# LED_BOARD_1st_Iteration.net
KiCad netlist of a schematic drawn in EAGLE
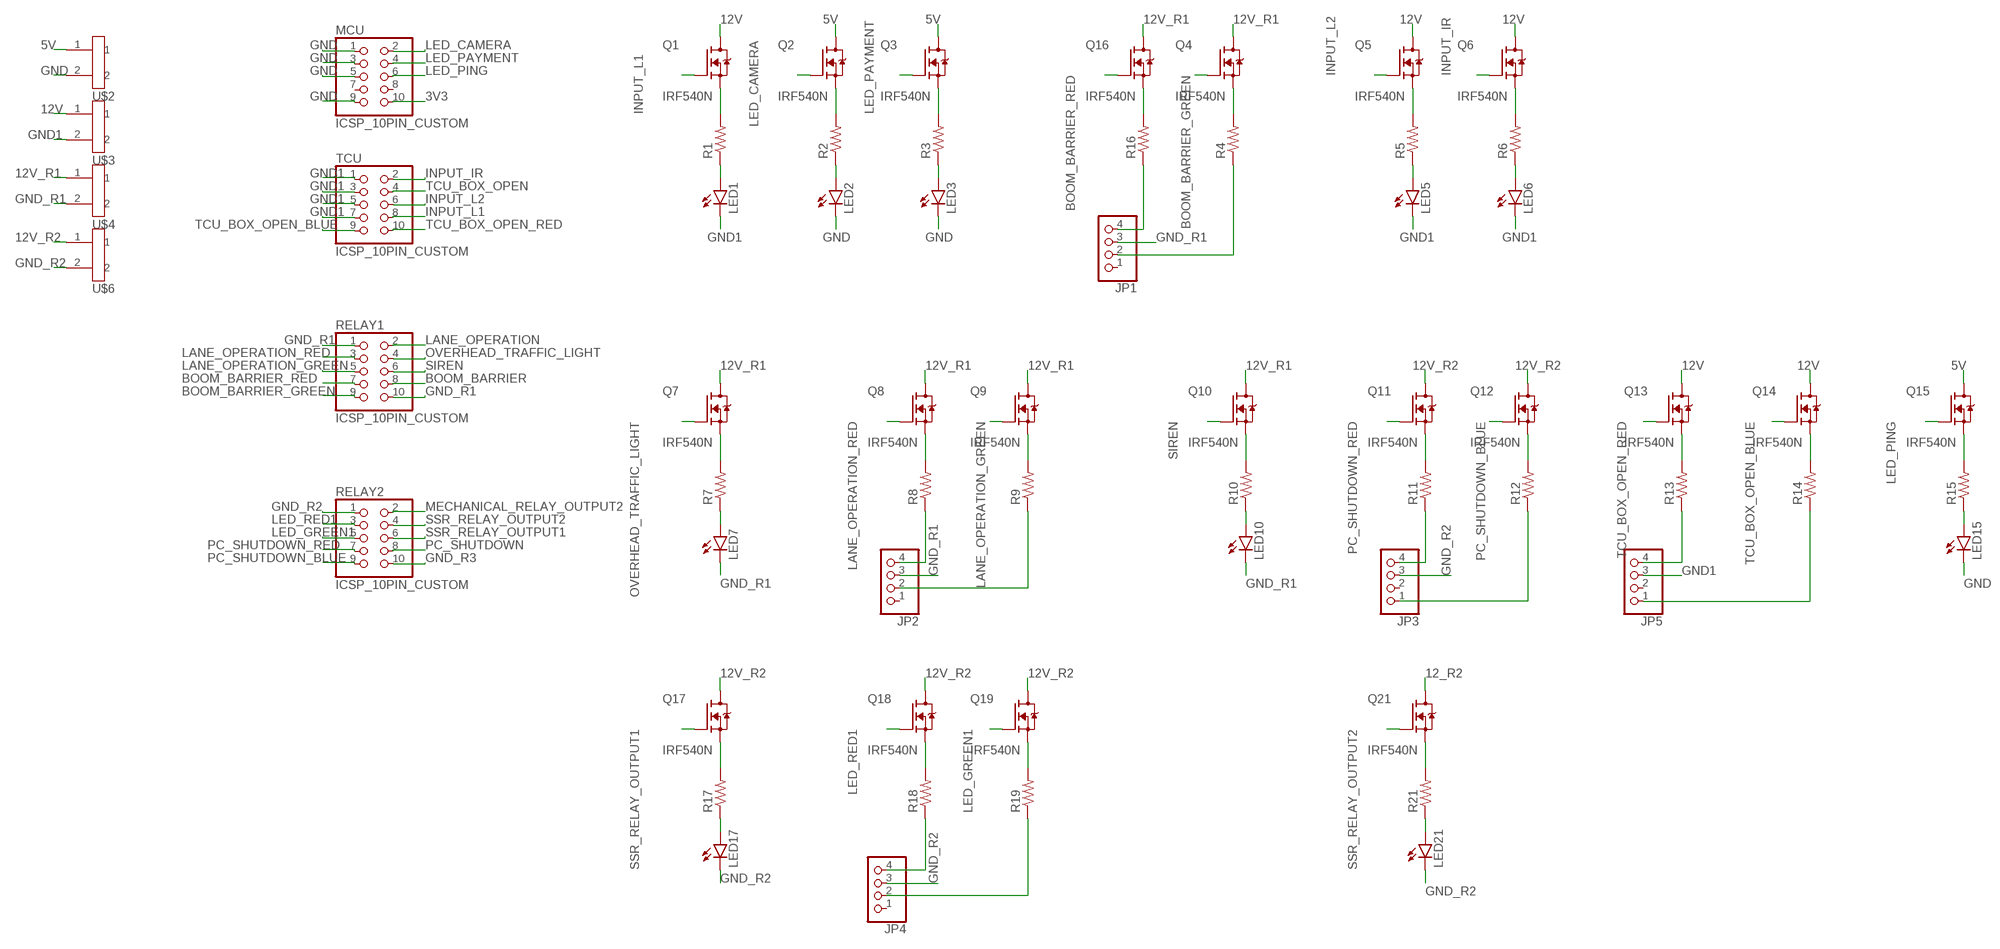
[diagram p0: schematic, sheet 1]

(export (version "E")
  (design (tool "Eeschema 10.0.6"))
  (components
    (comp (ref "JP1")
      (value "PINHD-1X4")
      (footprint "eagle-import:1X04")
      (libsource (lib "eagle-import") (part "PINHD-1X4"))
    )
    (comp (ref "JP2")
      (value "PINHD-1X4")
      (footprint "eagle-import:1X04")
      (libsource (lib "eagle-import") (part "PINHD-1X4"))
    )
    (comp (ref "JP3")
      (value "PINHD-1X4")
      (footprint "eagle-import:1X04")
      (libsource (lib "eagle-import") (part "PINHD-1X4"))
    )
    (comp (ref "JP4")
      (value "PINHD-1X4")
      (footprint "eagle-import:1X04")
      (libsource (lib "eagle-import") (part "PINHD-1X4"))
    )
    (comp (ref "JP5")
      (value "PINHD-1X4")
      (footprint "eagle-import:1X04")
      (libsource (lib "eagle-import") (part "PINHD-1X4"))
    )
    (comp (ref "LED1")
      (value "LED")
      (footprint "eagle-import:LED")
      (libsource (lib "eagle-import") (part "LED"))
    )
    (comp (ref "LED2")
      (value "LED")
      (footprint "eagle-import:LED")
      (libsource (lib "eagle-import") (part "LED"))
    )
    (comp (ref "LED3")
      (value "LED")
      (footprint "eagle-import:LED")
      (libsource (lib "eagle-import") (part "LED"))
    )
    (comp (ref "LED5")
      (value "LED")
      (footprint "eagle-import:LED")
      (libsource (lib "eagle-import") (part "LED"))
    )
    (comp (ref "LED6")
      (value "LED")
      (footprint "eagle-import:LED")
      (libsource (lib "eagle-import") (part "LED"))
    )
    (comp (ref "LED7")
      (value "LED")
      (footprint "eagle-import:LED")
      (libsource (lib "eagle-import") (part "LED"))
    )
    (comp (ref "LED10")
      (value "LED")
      (footprint "eagle-import:LED")
      (libsource (lib "eagle-import") (part "LED"))
    )
    (comp (ref "LED15")
      (value "LED")
      (footprint "eagle-import:LED")
      (libsource (lib "eagle-import") (part "LED"))
    )
    (comp (ref "LED17")
      (value "LED")
      (footprint "eagle-import:LED")
      (libsource (lib "eagle-import") (part "LED"))
    )
    (comp (ref "LED21")
      (value "LED")
      (footprint "eagle-import:LED")
      (libsource (lib "eagle-import") (part "LED"))
    )
    (comp (ref "MCU")
      (value "ICSP_10PIN_CUSTOM")
      (footprint "eagle-import:ICSP_10PIN_CUSTOM")
      (libsource (lib "eagle-import") (part "ICSP_10PIN_CUSTOM"))
    )
    (comp (ref "Q1")
      (value "IRF540N")
      (footprint "eagle-import:TO254P1054X469X1930-3")
      (fields (field (name "MF") "Infineon Technologies"))
      (libsource (lib "eagle-import") (part "IRF540N"))
    )
    (comp (ref "Q2")
      (value "IRF540N")
      (footprint "eagle-import:TO254P1054X469X1930-3")
      (fields (field (name "MF") "Infineon Technologies"))
      (libsource (lib "eagle-import") (part "IRF540N"))
    )
    (comp (ref "Q3")
      (value "IRF540N")
      (footprint "eagle-import:TO254P1054X469X1930-3")
      (fields (field (name "MF") "Infineon Technologies"))
      (libsource (lib "eagle-import") (part "IRF540N"))
    )
    (comp (ref "Q4")
      (value "IRF540N")
      (footprint "eagle-import:TO254P1054X469X1930-3")
      (fields (field (name "MF") "Infineon Technologies"))
      (libsource (lib "eagle-import") (part "IRF540N"))
    )
    (comp (ref "Q5")
      (value "IRF540N")
      (footprint "eagle-import:TO254P1054X469X1930-3")
      (fields (field (name "MF") "Infineon Technologies"))
      (libsource (lib "eagle-import") (part "IRF540N"))
    )
    (comp (ref "Q6")
      (value "IRF540N")
      (footprint "eagle-import:TO254P1054X469X1930-3")
      (fields (field (name "MF") "Infineon Technologies"))
      (libsource (lib "eagle-import") (part "IRF540N"))
    )
    (comp (ref "Q7")
      (value "IRF540N")
      (footprint "eagle-import:TO254P1054X469X1930-3")
      (fields (field (name "MF") "Infineon Technologies"))
      (libsource (lib "eagle-import") (part "IRF540N"))
    )
    (comp (ref "Q8")
      (value "IRF540N")
      (footprint "eagle-import:TO254P1054X469X1930-3")
      (fields (field (name "MF") "Infineon Technologies"))
      (libsource (lib "eagle-import") (part "IRF540N"))
    )
    (comp (ref "Q9")
      (value "IRF540N")
      (footprint "eagle-import:TO254P1054X469X1930-3")
      (fields (field (name "MF") "Infineon Technologies"))
      (libsource (lib "eagle-import") (part "IRF540N"))
    )
    (comp (ref "Q10")
      (value "IRF540N")
      (footprint "eagle-import:TO254P1054X469X1930-3")
      (fields (field (name "MF") "Infineon Technologies"))
      (libsource (lib "eagle-import") (part "IRF540N"))
    )
    (comp (ref "Q11")
      (value "IRF540N")
      (footprint "eagle-import:TO254P1054X469X1930-3")
      (fields (field (name "MF") "Infineon Technologies"))
      (libsource (lib "eagle-import") (part "IRF540N"))
    )
    (comp (ref "Q12")
      (value "IRF540N")
      (footprint "eagle-import:TO254P1054X469X1930-3")
      (fields (field (name "MF") "Infineon Technologies"))
      (libsource (lib "eagle-import") (part "IRF540N"))
    )
    (comp (ref "Q13")
      (value "IRF540N")
      (footprint "eagle-import:TO254P1054X469X1930-3")
      (fields (field (name "MF") "Infineon Technologies"))
      (libsource (lib "eagle-import") (part "IRF540N"))
    )
    (comp (ref "Q14")
      (value "IRF540N")
      (footprint "eagle-import:TO254P1054X469X1930-3")
      (fields (field (name "MF") "Infineon Technologies"))
      (libsource (lib "eagle-import") (part "IRF540N"))
    )
    (comp (ref "Q15")
      (value "IRF540N")
      (footprint "eagle-import:TO254P1054X469X1930-3")
      (fields (field (name "MF") "Infineon Technologies"))
      (libsource (lib "eagle-import") (part "IRF540N"))
    )
    (comp (ref "Q16")
      (value "IRF540N")
      (footprint "eagle-import:TO254P1054X469X1930-3")
      (fields (field (name "MF") "Infineon Technologies"))
      (libsource (lib "eagle-import") (part "IRF540N"))
    )
    (comp (ref "Q17")
      (value "IRF540N")
      (footprint "eagle-import:TO254P1054X469X1930-3")
      (fields (field (name "MF") "Infineon Technologies"))
      (libsource (lib "eagle-import") (part "IRF540N"))
    )
    (comp (ref "Q18")
      (value "IRF540N")
      (footprint "eagle-import:TO254P1054X469X1930-3")
      (fields (field (name "MF") "Infineon Technologies"))
      (libsource (lib "eagle-import") (part "IRF540N"))
    )
    (comp (ref "Q19")
      (value "IRF540N")
      (footprint "eagle-import:TO254P1054X469X1930-3")
      (fields (field (name "MF") "Infineon Technologies"))
      (libsource (lib "eagle-import") (part "IRF540N"))
    )
    (comp (ref "Q21")
      (value "IRF540N")
      (footprint "eagle-import:TO254P1054X469X1930-3")
      (fields (field (name "MF") "Infineon Technologies"))
      (libsource (lib "eagle-import") (part "IRF540N"))
    )
    (comp (ref "R1")
      (value "RESISTOR")
      (footprint "eagle-import:RESISTOR")
      (libsource (lib "eagle-import") (part "RESISTOR"))
    )
    (comp (ref "R2")
      (value "RESISTOR")
      (footprint "eagle-import:RESISTOR")
      (libsource (lib "eagle-import") (part "RESISTOR"))
    )
    (comp (ref "R3")
      (value "RESISTOR")
      (footprint "eagle-import:RESISTOR")
      (libsource (lib "eagle-import") (part "RESISTOR"))
    )
    (comp (ref "R4")
      (value "RESISTOR")
      (footprint "eagle-import:RESISTOR")
      (libsource (lib "eagle-import") (part "RESISTOR"))
    )
    (comp (ref "R5")
      (value "RESISTOR")
      (footprint "eagle-import:RESISTOR")
      (libsource (lib "eagle-import") (part "RESISTOR"))
    )
    (comp (ref "R6")
      (value "RESISTOR")
      (footprint "eagle-import:RESISTOR")
      (libsource (lib "eagle-import") (part "RESISTOR"))
    )
    (comp (ref "R7")
      (value "RESISTOR")
      (footprint "eagle-import:RESISTOR")
      (libsource (lib "eagle-import") (part "RESISTOR"))
    )
    (comp (ref "R8")
      (value "RESISTOR")
      (footprint "eagle-import:RESISTOR")
      (libsource (lib "eagle-import") (part "RESISTOR"))
    )
    (comp (ref "R9")
      (value "RESISTOR")
      (footprint "eagle-import:RESISTOR")
      (libsource (lib "eagle-import") (part "RESISTOR"))
    )
    (comp (ref "R10")
      (value "RESISTOR")
      (footprint "eagle-import:RESISTOR")
      (libsource (lib "eagle-import") (part "RESISTOR"))
    )
    (comp (ref "R11")
      (value "RESISTOR")
      (footprint "eagle-import:RESISTOR")
      (libsource (lib "eagle-import") (part "RESISTOR"))
    )
    (comp (ref "R12")
      (value "RESISTOR")
      (footprint "eagle-import:RESISTOR")
      (libsource (lib "eagle-import") (part "RESISTOR"))
    )
    (comp (ref "R13")
      (value "RESISTOR")
      (footprint "eagle-import:RESISTOR")
      (libsource (lib "eagle-import") (part "RESISTOR"))
    )
    (comp (ref "R14")
      (value "RESISTOR")
      (footprint "eagle-import:RESISTOR")
      (libsource (lib "eagle-import") (part "RESISTOR"))
    )
    (comp (ref "R15")
      (value "RESISTOR")
      (footprint "eagle-import:RESISTOR")
      (libsource (lib "eagle-import") (part "RESISTOR"))
    )
    (comp (ref "R16")
      (value "RESISTOR")
      (footprint "eagle-import:RESISTOR")
      (libsource (lib "eagle-import") (part "RESISTOR"))
    )
    (comp (ref "R17")
      (value "RESISTOR")
      (footprint "eagle-import:RESISTOR")
      (libsource (lib "eagle-import") (part "RESISTOR"))
    )
    (comp (ref "R18")
      (value "RESISTOR")
      (footprint "eagle-import:RESISTOR")
      (libsource (lib "eagle-import") (part "RESISTOR"))
    )
    (comp (ref "R19")
      (value "RESISTOR")
      (footprint "eagle-import:RESISTOR")
      (libsource (lib "eagle-import") (part "RESISTOR"))
    )
    (comp (ref "R21")
      (value "RESISTOR")
      (footprint "eagle-import:RESISTOR")
      (libsource (lib "eagle-import") (part "RESISTOR"))
    )
    (comp (ref "RELAY1")
      (value "ICSP_10PIN_CUSTOM")
      (footprint "eagle-import:ICSP_10PIN_CUSTOM")
      (libsource (lib "eagle-import") (part "ICSP_10PIN_CUSTOM"))
    )
    (comp (ref "RELAY2")
      (value "ICSP_10PIN_CUSTOM")
      (footprint "eagle-import:ICSP_10PIN_CUSTOM")
      (libsource (lib "eagle-import") (part "ICSP_10PIN_CUSTOM"))
    )
    (comp (ref "TCU")
      (value "ICSP_10PIN_CUSTOM")
      (footprint "eagle-import:ICSP_10PIN_CUSTOM")
      (libsource (lib "eagle-import") (part "ICSP_10PIN_CUSTOM"))
    )
    (comp (ref "U$2")
      (value "GREEN_PLUG_90_2")
      (footprint "eagle-import:GREEN_PLUG_90_2")
      (libsource (lib "eagle-import") (part "GREEN_PLUG_90_2"))
    )
    (comp (ref "U$3")
      (value "GREEN_PLUG_90_2")
      (footprint "eagle-import:GREEN_PLUG_90_2")
      (libsource (lib "eagle-import") (part "GREEN_PLUG_90_2"))
    )
    (comp (ref "U$4")
      (value "GREEN_PLUG_90_2")
      (footprint "eagle-import:GREEN_PLUG_90_2")
      (libsource (lib "eagle-import") (part "GREEN_PLUG_90_2"))
    )
    (comp (ref "U$6")
      (value "GREEN_PLUG_90_2")
      (footprint "eagle-import:GREEN_PLUG_90_2")
      (libsource (lib "eagle-import") (part "GREEN_PLUG_90_2"))
    )
  )
  (nets
    (net (code "1") (name "/3V3") (class "Default")
      (node (ref "MCU") (pin "10") (pinfunction "10_10") (pintype "passive"))
    )
    (net (code "2") (name "/5V") (class "Default")
      (node (ref "Q15") (pin "2") (pinfunction "D_2") (pintype "passive"))
      (node (ref "Q2") (pin "2") (pinfunction "D_2") (pintype "passive"))
      (node (ref "Q3") (pin "2") (pinfunction "D_2") (pintype "passive"))
      (node (ref "U$2") (pin "1") (pinfunction "1_1") (pintype "passive"))
    )
    (net (code "3") (name "/12V") (class "Default")
      (node (ref "Q1") (pin "2") (pinfunction "D_2") (pintype "passive"))
      (node (ref "Q13") (pin "2") (pinfunction "D_2") (pintype "passive"))
      (node (ref "Q14") (pin "2") (pinfunction "D_2") (pintype "passive"))
      (node (ref "Q5") (pin "2") (pinfunction "D_2") (pintype "passive"))
      (node (ref "Q6") (pin "2") (pinfunction "D_2") (pintype "passive"))
      (node (ref "U$3") (pin "1") (pinfunction "1_1") (pintype "passive"))
    )
    (net (code "4") (name "/12V_R1") (class "Default")
      (node (ref "Q10") (pin "2") (pinfunction "D_2") (pintype "passive"))
      (node (ref "Q16") (pin "2") (pinfunction "D_2") (pintype "passive"))
      (node (ref "Q4") (pin "2") (pinfunction "D_2") (pintype "passive"))
      (node (ref "Q7") (pin "2") (pinfunction "D_2") (pintype "passive"))
      (node (ref "Q8") (pin "2") (pinfunction "D_2") (pintype "passive"))
      (node (ref "Q9") (pin "2") (pinfunction "D_2") (pintype "passive"))
      (node (ref "U$4") (pin "1") (pinfunction "1_1") (pintype "passive"))
    )
    (net (code "5") (name "/12V_R2") (class "Default")
      (node (ref "Q11") (pin "2") (pinfunction "D_2") (pintype "passive"))
      (node (ref "Q12") (pin "2") (pinfunction "D_2") (pintype "passive"))
      (node (ref "Q17") (pin "2") (pinfunction "D_2") (pintype "passive"))
      (node (ref "Q18") (pin "2") (pinfunction "D_2") (pintype "passive"))
      (node (ref "Q19") (pin "2") (pinfunction "D_2") (pintype "passive"))
      (node (ref "U$6") (pin "1") (pinfunction "1_1") (pintype "passive"))
    )
    (net (code "6") (name "/12_R2") (class "Default")
      (node (ref "Q21") (pin "2") (pinfunction "D_2") (pintype "passive"))
    )
    (net (code "7") (name "/BOOM_BARRIER") (class "Default")
      (node (ref "RELAY1") (pin "8") (pinfunction "8_8") (pintype "passive"))
    )
    (net (code "8") (name "/BOOM_BARRIER_GREEN") (class "Default")
      (node (ref "Q4") (pin "1") (pinfunction "G_1") (pintype "passive"))
      (node (ref "RELAY1") (pin "9") (pinfunction "9_9") (pintype "passive"))
    )
    (net (code "9") (name "/BOOM_BARRIER_RED") (class "Default")
      (node (ref "Q16") (pin "1") (pinfunction "G_1") (pintype "passive"))
      (node (ref "RELAY1") (pin "7") (pinfunction "7_7") (pintype "passive"))
    )
    (net (code "10") (name "/GND") (class "Default")
      (node (ref "LED15") (pin "K") (pinfunction "C_K") (pintype "passive"))
      (node (ref "LED2") (pin "K") (pinfunction "C_K") (pintype "passive"))
      (node (ref "LED3") (pin "K") (pinfunction "C_K") (pintype "passive"))
      (node (ref "MCU") (pin "1") (pinfunction "1_1") (pintype "passive"))
      (node (ref "MCU") (pin "3") (pinfunction "3_3") (pintype "passive"))
      (node (ref "MCU") (pin "5") (pinfunction "5_5") (pintype "passive"))
      (node (ref "MCU") (pin "9") (pinfunction "9_9") (pintype "passive"))
      (node (ref "U$2") (pin "2") (pinfunction "2_2") (pintype "passive"))
    )
    (net (code "11") (name "/GND1") (class "Default")
      (node (ref "JP5") (pin "3") (pinfunction "3_3") (pintype "passive"))
      (node (ref "LED1") (pin "K") (pinfunction "C_K") (pintype "passive"))
      (node (ref "LED5") (pin "K") (pinfunction "C_K") (pintype "passive"))
      (node (ref "LED6") (pin "K") (pinfunction "C_K") (pintype "passive"))
      (node (ref "TCU") (pin "1") (pinfunction "1_1") (pintype "passive"))
      (node (ref "TCU") (pin "3") (pinfunction "3_3") (pintype "passive"))
      (node (ref "TCU") (pin "5") (pinfunction "5_5") (pintype "passive"))
      (node (ref "TCU") (pin "7") (pinfunction "7_7") (pintype "passive"))
      (node (ref "U$3") (pin "2") (pinfunction "2_2") (pintype "passive"))
    )
    (net (code "12") (name "/GND_R1") (class "Default")
      (node (ref "JP1") (pin "3") (pinfunction "3_3") (pintype "passive"))
      (node (ref "JP2") (pin "3") (pinfunction "3_3") (pintype "passive"))
      (node (ref "LED10") (pin "K") (pinfunction "C_K") (pintype "passive"))
      (node (ref "LED7") (pin "K") (pinfunction "C_K") (pintype "passive"))
      (node (ref "RELAY1") (pin "1") (pinfunction "1_1") (pintype "passive"))
      (node (ref "RELAY1") (pin "10") (pinfunction "10_10") (pintype "passive"))
      (node (ref "U$4") (pin "2") (pinfunction "2_2") (pintype "passive"))
    )
    (net (code "13") (name "/GND_R2") (class "Default")
      (node (ref "JP3") (pin "3") (pinfunction "3_3") (pintype "passive"))
      (node (ref "JP4") (pin "3") (pinfunction "3_3") (pintype "passive"))
      (node (ref "LED17") (pin "K") (pinfunction "C_K") (pintype "passive"))
      (node (ref "LED21") (pin "K") (pinfunction "C_K") (pintype "passive"))
      (node (ref "RELAY2") (pin "1") (pinfunction "1_1") (pintype "passive"))
      (node (ref "U$6") (pin "2") (pinfunction "2_2") (pintype "passive"))
    )
    (net (code "14") (name "/GND_R3") (class "Default")
      (node (ref "RELAY2") (pin "10") (pinfunction "10_10") (pintype "passive"))
    )
    (net (code "15") (name "/INPUT_IR") (class "Default")
      (node (ref "Q6") (pin "1") (pinfunction "G_1") (pintype "passive"))
      (node (ref "TCU") (pin "2") (pinfunction "2_2") (pintype "passive"))
    )
    (net (code "16") (name "/INPUT_L1") (class "Default")
      (node (ref "Q1") (pin "1") (pinfunction "G_1") (pintype "passive"))
      (node (ref "TCU") (pin "8") (pinfunction "8_8") (pintype "passive"))
    )
    (net (code "17") (name "/INPUT_L2") (class "Default")
      (node (ref "Q5") (pin "1") (pinfunction "G_1") (pintype "passive"))
      (node (ref "TCU") (pin "6") (pinfunction "6_6") (pintype "passive"))
    )
    (net (code "18") (name "/LANE_OPERATION") (class "Default")
      (node (ref "RELAY1") (pin "2") (pinfunction "2_2") (pintype "passive"))
    )
    (net (code "19") (name "/LANE_OPERATION_GREEN") (class "Default")
      (node (ref "Q9") (pin "1") (pinfunction "G_1") (pintype "passive"))
      (node (ref "RELAY1") (pin "5") (pinfunction "5_5") (pintype "passive"))
    )
    (net (code "20") (name "/LANE_OPERATION_RED") (class "Default")
      (node (ref "Q8") (pin "1") (pinfunction "G_1") (pintype "passive"))
      (node (ref "RELAY1") (pin "3") (pinfunction "3_3") (pintype "passive"))
    )
    (net (code "21") (name "/LED_CAMERA") (class "Default")
      (node (ref "MCU") (pin "2") (pinfunction "2_2") (pintype "passive"))
      (node (ref "Q2") (pin "1") (pinfunction "G_1") (pintype "passive"))
    )
    (net (code "22") (name "/LED_GREEN1") (class "Default")
      (node (ref "Q19") (pin "1") (pinfunction "G_1") (pintype "passive"))
      (node (ref "RELAY2") (pin "5") (pinfunction "5_5") (pintype "passive"))
    )
    (net (code "23") (name "/LED_PAYMENT") (class "Default")
      (node (ref "MCU") (pin "4") (pinfunction "4_4") (pintype "passive"))
      (node (ref "Q3") (pin "1") (pinfunction "G_1") (pintype "passive"))
    )
    (net (code "24") (name "/LED_PING") (class "Default")
      (node (ref "MCU") (pin "6") (pinfunction "6_6") (pintype "passive"))
      (node (ref "Q15") (pin "1") (pinfunction "G_1") (pintype "passive"))
    )
    (net (code "25") (name "/LED_RED1") (class "Default")
      (node (ref "Q18") (pin "1") (pinfunction "G_1") (pintype "passive"))
      (node (ref "RELAY2") (pin "3") (pinfunction "3_3") (pintype "passive"))
    )
    (net (code "26") (name "/MECHANICAL_RELAY_OUTPUT2") (class "Default")
      (node (ref "RELAY2") (pin "2") (pinfunction "2_2") (pintype "passive"))
    )
    (net (code "27") (name "/OVERHEAD_TRAFFIC_LIGHT") (class "Default")
      (node (ref "Q7") (pin "1") (pinfunction "G_1") (pintype "passive"))
      (node (ref "RELAY1") (pin "4") (pinfunction "4_4") (pintype "passive"))
    )
    (net (code "28") (name "/PC_SHUTDOWN") (class "Default")
      (node (ref "RELAY2") (pin "8") (pinfunction "8_8") (pintype "passive"))
    )
    (net (code "29") (name "/PC_SHUTDOWN_BLUE") (class "Default")
      (node (ref "Q12") (pin "1") (pinfunction "G_1") (pintype "passive"))
      (node (ref "RELAY2") (pin "9") (pinfunction "9_9") (pintype "passive"))
    )
    (net (code "30") (name "/PC_SHUTDOWN_RED") (class "Default")
      (node (ref "Q11") (pin "1") (pinfunction "G_1") (pintype "passive"))
      (node (ref "RELAY2") (pin "7") (pinfunction "7_7") (pintype "passive"))
    )
    (net (code "31") (name "/SIREN") (class "Default")
      (node (ref "Q10") (pin "1") (pinfunction "G_1") (pintype "passive"))
      (node (ref "RELAY1") (pin "6") (pinfunction "6_6") (pintype "passive"))
    )
    (net (code "32") (name "/SSR_RELAY_OUTPUT1") (class "Default")
      (node (ref "Q17") (pin "1") (pinfunction "G_1") (pintype "passive"))
      (node (ref "RELAY2") (pin "6") (pinfunction "6_6") (pintype "passive"))
    )
    (net (code "33") (name "/SSR_RELAY_OUTPUT2") (class "Default")
      (node (ref "Q21") (pin "1") (pinfunction "G_1") (pintype "passive"))
      (node (ref "RELAY2") (pin "4") (pinfunction "4_4") (pintype "passive"))
    )
    (net (code "34") (name "/TCU_BOX_OPEN") (class "Default")
      (node (ref "TCU") (pin "4") (pinfunction "4_4") (pintype "passive"))
    )
    (net (code "35") (name "/TCU_BOX_OPEN_BLUE") (class "Default")
      (node (ref "Q14") (pin "1") (pinfunction "G_1") (pintype "passive"))
      (node (ref "TCU") (pin "9") (pinfunction "9_9") (pintype "passive"))
    )
    (net (code "36") (name "/TCU_BOX_OPEN_RED") (class "Default")
      (node (ref "Q13") (pin "1") (pinfunction "G_1") (pintype "passive"))
      (node (ref "TCU") (pin "10") (pinfunction "10_10") (pintype "passive"))
    )
    (net (code "37") (name "Net-(JP1-Pad2)") (class "Default")
      (node (ref "JP1") (pin "2") (pinfunction "2_2") (pintype "passive"))
      (node (ref "R4") (pin "1") (pinfunction "1_1") (pintype "passive"))
    )
    (net (code "38") (name "Net-(JP1-Pad4)") (class "Default")
      (node (ref "JP1") (pin "4") (pinfunction "4_4") (pintype "passive"))
      (node (ref "R16") (pin "1") (pinfunction "1_1") (pintype "passive"))
    )
    (net (code "39") (name "Net-(JP2-Pad2)") (class "Default")
      (node (ref "JP2") (pin "2") (pinfunction "2_2") (pintype "passive"))
      (node (ref "R9") (pin "1") (pinfunction "1_1") (pintype "passive"))
    )
    (net (code "40") (name "Net-(JP2-Pad4)") (class "Default")
      (node (ref "JP2") (pin "4") (pinfunction "4_4") (pintype "passive"))
      (node (ref "R8") (pin "1") (pinfunction "1_1") (pintype "passive"))
    )
    (net (code "41") (name "Net-(JP3-Pad1)") (class "Default")
      (node (ref "JP3") (pin "1") (pinfunction "1_1") (pintype "passive"))
      (node (ref "R12") (pin "1") (pinfunction "1_1") (pintype "passive"))
    )
    (net (code "42") (name "Net-(JP3-Pad4)") (class "Default")
      (node (ref "JP3") (pin "4") (pinfunction "4_4") (pintype "passive"))
      (node (ref "R11") (pin "1") (pinfunction "1_1") (pintype "passive"))
    )
    (net (code "43") (name "Net-(JP4-Pad2)") (class "Default")
      (node (ref "JP4") (pin "2") (pinfunction "2_2") (pintype "passive"))
      (node (ref "R19") (pin "1") (pinfunction "1_1") (pintype "passive"))
    )
    (net (code "44") (name "Net-(JP4-Pad4)") (class "Default")
      (node (ref "JP4") (pin "4") (pinfunction "4_4") (pintype "passive"))
      (node (ref "R18") (pin "1") (pinfunction "1_1") (pintype "passive"))
    )
    (net (code "45") (name "Net-(JP5-Pad1)") (class "Default")
      (node (ref "JP5") (pin "1") (pinfunction "1_1") (pintype "passive"))
      (node (ref "R14") (pin "1") (pinfunction "1_1") (pintype "passive"))
    )
    (net (code "46") (name "Net-(JP5-Pad4)") (class "Default")
      (node (ref "JP5") (pin "4") (pinfunction "4_4") (pintype "passive"))
      (node (ref "R13") (pin "1") (pinfunction "1_1") (pintype "passive"))
    )
    (net (code "47") (name "Net-(LED1-PadA)") (class "Default")
      (node (ref "LED1") (pin "A") (pinfunction "A_A") (pintype "passive"))
      (node (ref "R1") (pin "1") (pinfunction "1_1") (pintype "passive"))
    )
    (net (code "48") (name "Net-(LED2-PadA)") (class "Default")
      (node (ref "LED2") (pin "A") (pinfunction "A_A") (pintype "passive"))
      (node (ref "R2") (pin "1") (pinfunction "1_1") (pintype "passive"))
    )
    (net (code "49") (name "Net-(LED3-PadA)") (class "Default")
      (node (ref "LED3") (pin "A") (pinfunction "A_A") (pintype "passive"))
      (node (ref "R3") (pin "1") (pinfunction "1_1") (pintype "passive"))
    )
    (net (code "50") (name "Net-(LED5-PadA)") (class "Default")
      (node (ref "LED5") (pin "A") (pinfunction "A_A") (pintype "passive"))
      (node (ref "R5") (pin "1") (pinfunction "1_1") (pintype "passive"))
    )
    (net (code "51") (name "Net-(LED6-PadA)") (class "Default")
      (node (ref "LED6") (pin "A") (pinfunction "A_A") (pintype "passive"))
      (node (ref "R6") (pin "1") (pinfunction "1_1") (pintype "passive"))
    )
    (net (code "52") (name "Net-(LED7-PadA)") (class "Default")
      (node (ref "LED7") (pin "A") (pinfunction "A_A") (pintype "passive"))
      (node (ref "R7") (pin "1") (pinfunction "1_1") (pintype "passive"))
    )
    (net (code "53") (name "Net-(LED10-PadA)") (class "Default")
      (node (ref "LED10") (pin "A") (pinfunction "A_A") (pintype "passive"))
      (node (ref "R10") (pin "1") (pinfunction "1_1") (pintype "passive"))
    )
    (net (code "54") (name "Net-(LED15-PadA)") (class "Default")
      (node (ref "LED15") (pin "A") (pinfunction "A_A") (pintype "passive"))
      (node (ref "R15") (pin "1") (pinfunction "1_1") (pintype "passive"))
    )
    (net (code "55") (name "Net-(LED17-PadA)") (class "Default")
      (node (ref "LED17") (pin "A") (pinfunction "A_A") (pintype "passive"))
      (node (ref "R17") (pin "1") (pinfunction "1_1") (pintype "passive"))
    )
    (net (code "56") (name "Net-(LED21-PadA)") (class "Default")
      (node (ref "LED21") (pin "A") (pinfunction "A_A") (pintype "passive"))
      (node (ref "R21") (pin "1") (pinfunction "1_1") (pintype "passive"))
    )
    (net (code "57") (name "Net-(Q1-S)") (class "Default")
      (node (ref "Q1") (pin "3") (pinfunction "S_3") (pintype "passive"))
      (node (ref "R1") (pin "2") (pinfunction "2_2") (pintype "passive"))
    )
    (net (code "58") (name "Net-(Q2-S)") (class "Default")
      (node (ref "Q2") (pin "3") (pinfunction "S_3") (pintype "passive"))
      (node (ref "R2") (pin "2") (pinfunction "2_2") (pintype "passive"))
    )
    (net (code "59") (name "Net-(Q3-S)") (class "Default")
      (node (ref "Q3") (pin "3") (pinfunction "S_3") (pintype "passive"))
      (node (ref "R3") (pin "2") (pinfunction "2_2") (pintype "passive"))
    )
    (net (code "60") (name "Net-(Q4-S)") (class "Default")
      (node (ref "Q4") (pin "3") (pinfunction "S_3") (pintype "passive"))
      (node (ref "R4") (pin "2") (pinfunction "2_2") (pintype "passive"))
    )
    (net (code "61") (name "Net-(Q5-S)") (class "Default")
      (node (ref "Q5") (pin "3") (pinfunction "S_3") (pintype "passive"))
      (node (ref "R5") (pin "2") (pinfunction "2_2") (pintype "passive"))
    )
    (net (code "62") (name "Net-(Q6-S)") (class "Default")
      (node (ref "Q6") (pin "3") (pinfunction "S_3") (pintype "passive"))
      (node (ref "R6") (pin "2") (pinfunction "2_2") (pintype "passive"))
    )
    (net (code "63") (name "Net-(Q7-S)") (class "Default")
      (node (ref "Q7") (pin "3") (pinfunction "S_3") (pintype "passive"))
      (node (ref "R7") (pin "2") (pinfunction "2_2") (pintype "passive"))
    )
    (net (code "64") (name "Net-(Q8-S)") (class "Default")
      (node (ref "Q8") (pin "3") (pinfunction "S_3") (pintype "passive"))
      (node (ref "R8") (pin "2") (pinfunction "2_2") (pintype "passive"))
    )
    (net (code "65") (name "Net-(Q9-S)") (class "Default")
      (node (ref "Q9") (pin "3") (pinfunction "S_3") (pintype "passive"))
      (node (ref "R9") (pin "2") (pinfunction "2_2") (pintype "passive"))
    )
    (net (code "66") (name "Net-(Q10-S)") (class "Default")
      (node (ref "Q10") (pin "3") (pinfunction "S_3") (pintype "passive"))
      (node (ref "R10") (pin "2") (pinfunction "2_2") (pintype "passive"))
    )
    (net (code "67") (name "Net-(Q11-S)") (class "Default")
      (node (ref "Q11") (pin "3") (pinfunction "S_3") (pintype "passive"))
      (node (ref "R11") (pin "2") (pinfunction "2_2") (pintype "passive"))
    )
    (net (code "68") (name "Net-(Q12-S)") (class "Default")
      (node (ref "Q12") (pin "3") (pinfunction "S_3") (pintype "passive"))
      (node (ref "R12") (pin "2") (pinfunction "2_2") (pintype "passive"))
    )
    (net (code "69") (name "Net-(Q13-S)") (class "Default")
      (node (ref "Q13") (pin "3") (pinfunction "S_3") (pintype "passive"))
      (node (ref "R13") (pin "2") (pinfunction "2_2") (pintype "passive"))
    )
    (net (code "70") (name "Net-(Q14-S)") (class "Default")
      (node (ref "Q14") (pin "3") (pinfunction "S_3") (pintype "passive"))
      (node (ref "R14") (pin "2") (pinfunction "2_2") (pintype "passive"))
    )
    (net (code "71") (name "Net-(Q15-S)") (class "Default")
      (node (ref "Q15") (pin "3") (pinfunction "S_3") (pintype "passive"))
      (node (ref "R15") (pin "2") (pinfunction "2_2") (pintype "passive"))
    )
    (net (code "72") (name "Net-(Q16-S)") (class "Default")
      (node (ref "Q16") (pin "3") (pinfunction "S_3") (pintype "passive"))
      (node (ref "R16") (pin "2") (pinfunction "2_2") (pintype "passive"))
    )
    (net (code "73") (name "Net-(Q17-S)") (class "Default")
      (node (ref "Q17") (pin "3") (pinfunction "S_3") (pintype "passive"))
      (node (ref "R17") (pin "2") (pinfunction "2_2") (pintype "passive"))
    )
    (net (code "74") (name "Net-(Q18-S)") (class "Default")
      (node (ref "Q18") (pin "3") (pinfunction "S_3") (pintype "passive"))
      (node (ref "R18") (pin "2") (pinfunction "2_2") (pintype "passive"))
    )
    (net (code "75") (name "Net-(Q19-S)") (class "Default")
      (node (ref "Q19") (pin "3") (pinfunction "S_3") (pintype "passive"))
      (node (ref "R19") (pin "2") (pinfunction "2_2") (pintype "passive"))
    )
    (net (code "76") (name "Net-(Q21-S)") (class "Default")
      (node (ref "Q21") (pin "3") (pinfunction "S_3") (pintype "passive"))
      (node (ref "R21") (pin "2") (pinfunction "2_2") (pintype "passive"))
    )
    (net (code "77") (name "unconnected-(JP1-Pad1)") (class "Default")
      (node (ref "JP1") (pin "1") (pinfunction "1_1") (pintype "passive"))
    )
    (net (code "78") (name "unconnected-(JP2-Pad1)") (class "Default")
      (node (ref "JP2") (pin "1") (pinfunction "1_1") (pintype "passive"))
    )
    (net (code "79") (name "unconnected-(JP3-Pad2)") (class "Default")
      (node (ref "JP3") (pin "2") (pinfunction "2_2") (pintype "passive"))
    )
    (net (code "80") (name "unconnected-(JP4-Pad1)") (class "Default")
      (node (ref "JP4") (pin "1") (pinfunction "1_1") (pintype "passive"))
    )
    (net (code "81") (name "unconnected-(JP5-Pad2)") (class "Default")
      (node (ref "JP5") (pin "2") (pinfunction "2_2") (pintype "passive"))
    )
    (net (code "82") (name "unconnected-(MCU-Pad7)") (class "Default")
      (node (ref "MCU") (pin "7") (pinfunction "7_7") (pintype "passive"))
    )
    (net (code "83") (name "unconnected-(MCU-Pad8)") (class "Default")
      (node (ref "MCU") (pin "8") (pinfunction "8_8") (pintype "passive"))
    )
  )
)
